# JlinkV9SCH.net
KiCad netlist of a schematic drawn in Altium Designer
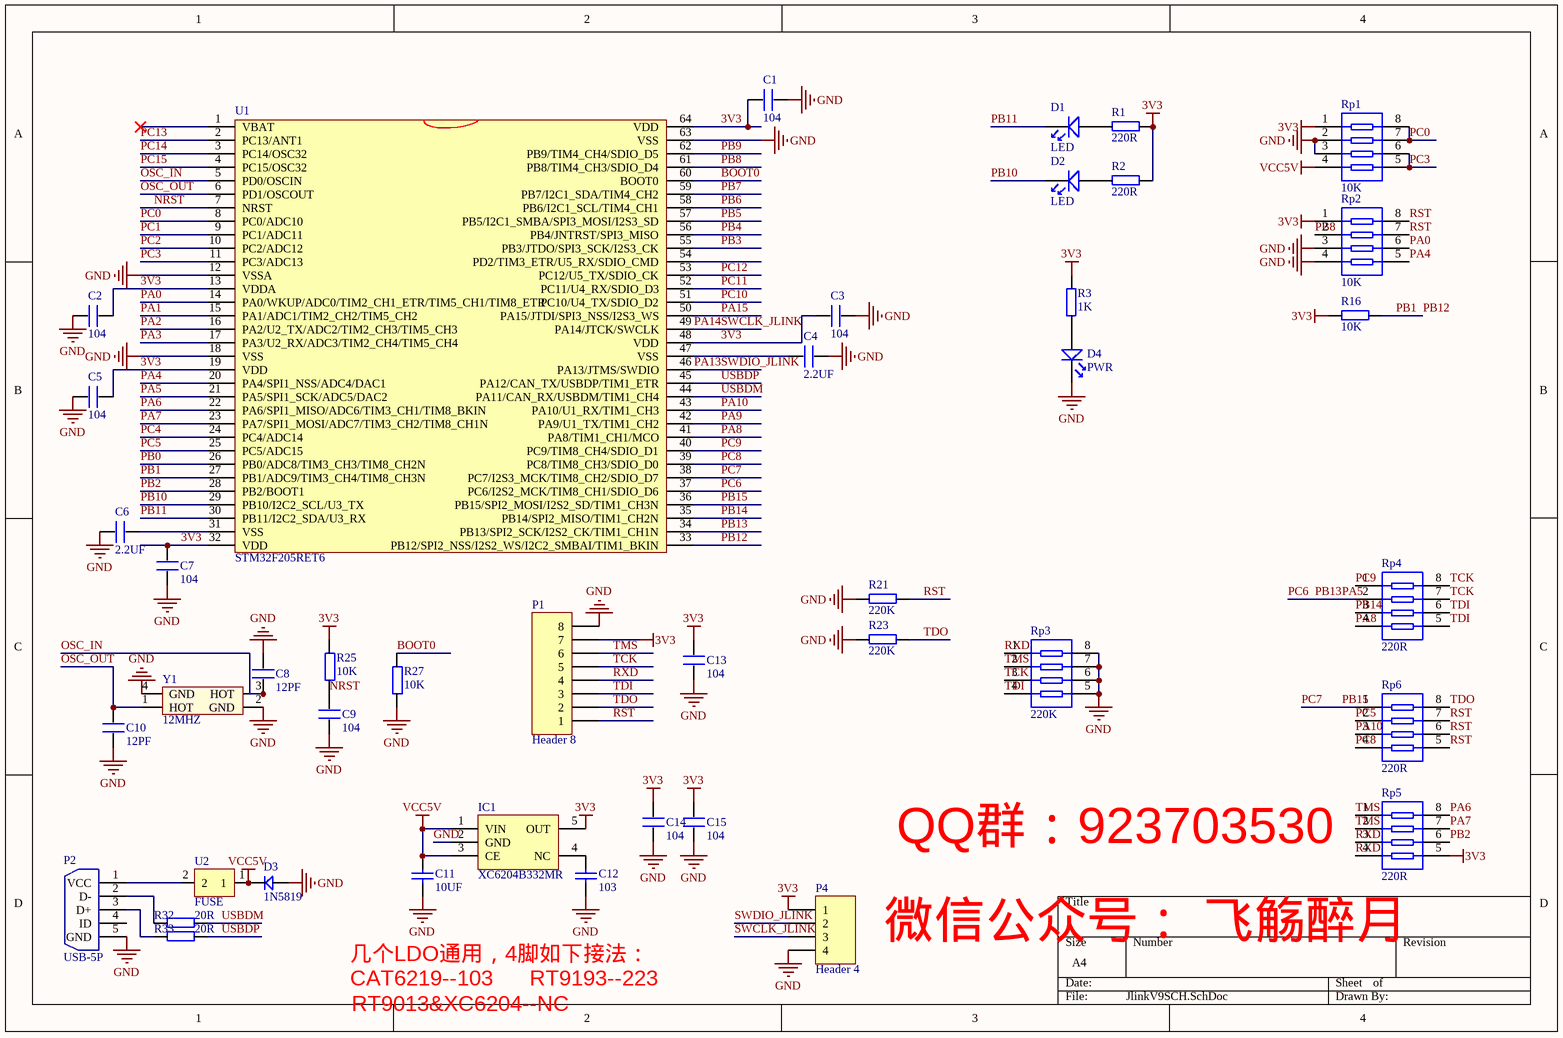
[diagram p0: JlinkV9SCH.SchDoc]

(export (version "E")
  (design (tool "Eeschema 10.0.6"))
  (components
    (comp (ref "C1") (value "104") (footprint "0402_C") (libsource (lib "myschlib") (part "C")))
    (comp (ref "C2") (value "104") (footprint "0402_C") (libsource (lib "myschlib") (part "C")))
    (comp (ref "C3") (value "104") (footprint "0402_C") (libsource (lib "myschlib") (part "C")))
    (comp (ref "C4") (value "2.2UF") (footprint "0402_C") (libsource (lib "myschlib") (part "C")))
    (comp (ref "C5") (value "104") (footprint "0402_C") (libsource (lib "myschlib") (part "C")))
    (comp (ref "C6") (value "2.2UF") (footprint "0402_C") (libsource (lib "myschlib") (part "C")))
    (comp (ref "C7") (value "104") (footprint "0402_C") (libsource (lib "myschlib") (part "C")))
    (comp (ref "C8") (value "12PF") (footprint "0402_C") (libsource (lib "myschlib") (part "C")))
    (comp (ref "C9") (value "104") (footprint "0402_C") (libsource (lib "myschlib") (part "C")))
    (comp (ref "C10") (value "12PF") (footprint "0402_C") (libsource (lib "myschlib") (part "C")))
    (comp (ref "C11")
      (value "10UF")
      (footprint "0603_C")
      (description "贴片电容")
      (libsource (lib "Miscellaneous Devices LC") (part "0603 10uF (106) 10% 10V"))
    )
    (comp (ref "C12")
      (value "103")
      (footprint "0402_C")
      (description "贴片电容")
      (libsource (lib "Miscellaneous Devices LC") (part "0402 10nF (103) 10% 50V"))
    )
    (comp (ref "C13") (value "104") (footprint "0603_C") (libsource (lib "myschlib") (part "C")))
    (comp (ref "C14") (value "104") (footprint "0603_C") (libsource (lib "myschlib") (part "C")))
    (comp (ref "C15") (value "104") (footprint "0603_C") (libsource (lib "myschlib") (part "C")))
    (comp (ref "D1") (value "LED") (footprint "SMDLED-0603") (libsource (lib "myschlib") (part "LED")))
    (comp (ref "D2") (value "LED") (footprint "SMDLED-0603") (libsource (lib "myschlib") (part "LED")))
    (comp (ref "D3") (value "1N5819") (footprint "mypcblib:SOD-323") (libsource (lib "myschlib") (part "D")))
    (comp (ref "D4") (value "PWR") (footprint "SMDLED-0603") (libsource (lib "myschlib") (part "LED")))
    (comp (ref "IC1")
      (value "XC6204B332MR")
      (footprint "SOT23-5L")
      (description "LDO")
      (fields (field (name "版权归属") "源创客"))
      (libsource (lib "myschlib") (part "LDO XC6204"))
    )
    (comp (ref "P1")
      (value "Header 8")
      (footprint "GH1.25-8P")
      (description "Header, 8-Pin")
      (fields (field (name "PUBLISHER") "Altium Limited"))
      (libsource (lib "myschlib") (part "Header 8"))
    )
    (comp (ref "P2")
      (value "USB-5P")
      (footprint "MICRO_USB")
      (description "微型USB母座")
      (fields (field (name "版权归属") "源创客"))
      (libsource (lib "myschlib") (part "USB-5P"))
    )
    (comp (ref "P4")
      (value "Header 4")
      (footprint "HDR1X4_SMD")
      (description "Header, 4-Pin")
      (fields (field (name "PUBLISHER") "Altium Limited"))
      (libsource (lib "myschlib") (part "Header 4"))
    )
    (comp (ref "R1") (value "220R") (footprint "0402_R") (libsource (lib "myschlib") (part "R")))
    (comp (ref "R2") (value "220R") (footprint "0402_R") (libsource (lib "myschlib") (part "R")))
    (comp (ref "R3") (value "1K") (footprint "0402_R") (libsource (lib "myschlib") (part "R")))
    (comp (ref "R16") (value "10K") (footprint "0402_R") (libsource (lib "myschlib") (part "R")))
    (comp (ref "R21") (value "220K") (footprint "0402_R") (libsource (lib "myschlib") (part "R")))
    (comp (ref "R23") (value "220K") (footprint "0402_R") (libsource (lib "myschlib") (part "R")))
    (comp (ref "R25") (value "10K") (footprint "0402_R") (libsource (lib "myschlib") (part "R")))
    (comp (ref "R27") (value "10K") (footprint "0402_R") (libsource (lib "myschlib") (part "R")))
    (comp (ref "R32") (value "20R") (footprint "0402_R") (libsource (lib "myschlib") (part "R")))
    (comp (ref "R33") (value "20R") (footprint "0402_R") (libsource (lib "myschlib") (part "R")))
    (comp (ref "Rp1")
      (value "10K")
      (footprint "mypcblib:0402_Rx4")
      (description "贴片排阻")
      (libsource (lib "myschlib") (part "R*4"))
    )
    (comp (ref "Rp2")
      (value "10K")
      (footprint "mypcblib:0402_Rx4")
      (description "贴片排阻")
      (libsource (lib "myschlib") (part "R*4"))
    )
    (comp (ref "Rp3")
      (value "220K")
      (footprint "mypcblib:0402_Rx4")
      (description "贴片排阻")
      (libsource (lib "myschlib") (part "R*4"))
    )
    (comp (ref "Rp4")
      (value "220R")
      (footprint "mypcblib:0402_Rx4")
      (description "贴片排阻")
      (libsource (lib "myschlib") (part "R*4"))
    )
    (comp (ref "Rp5")
      (value "220R")
      (footprint "mypcblib:0402_Rx4")
      (description "贴片排阻")
      (libsource (lib "myschlib") (part "R*4"))
    )
    (comp (ref "Rp6")
      (value "220R")
      (footprint "mypcblib:0402_Rx4")
      (description "贴片排阻")
      (libsource (lib "myschlib") (part "R*4"))
    )
    (comp (ref "U1")
      (value "STM32F205RET6")
      (footprint "STM-LQFP64_M")
      (libsource (lib "myschlib") (part "STM32F103RET6"))
    )
    (comp (ref "U2") (value "FUSE") (footprint "0603P") (libsource (lib "myschlib") (part "FUSE")))
    (comp (ref "Y1")
      (value "12MHZ")
      (footprint "XTAL3225")
      (description "3225贴片无源晶振")
      (libsource (lib "myschlib") (part "XTAL_3225"))
    )
  )
  (nets
    (net (code "1") (name "/BOOT0") (class "Default")
      (node (ref "R27") (pin "2") (pintype "passive"))
      (node (ref "U1") (pin "60") (pinfunction "BOOT0_60") (pintype "passive"))
    )
    (net (code "2") (name "/NRST") (class "Default")
      (node (ref "C9") (pin "2") (pintype "passive"))
      (node (ref "R25") (pin "1") (pintype "passive"))
      (node (ref "U1") (pin "7") (pinfunction "NRST_7") (pintype "passive"))
    )
    (net (code "3") (name "/OSC_IN") (class "Default")
      (node (ref "C8") (pin "1") (pintype "passive"))
      (node (ref "U1") (pin "5") (pinfunction "PD0/OSCIN_5") (pintype "passive"))
      (node (ref "Y1") (pin "3") (pinfunction "HOT_3") (pintype "passive"))
    )
    (net (code "4") (name "/OSC_OUT") (class "Default")
      (node (ref "C10") (pin "2") (pintype "passive"))
      (node (ref "U1") (pin "6") (pinfunction "PD1/OSCOUT_6") (pintype "passive"))
      (node (ref "Y1") (pin "1") (pinfunction "HOT_1") (pintype "passive"))
    )
    (net (code "5") (name "/PA0") (class "Default")
      (node (ref "Rp2") (pin "6") (pinfunction "6_6") (pintype "passive"))
      (node (ref "U1") (pin "14") (pinfunction "PA0/WKUP/ADC0/TIM2_CH1_ETR/TIM5_CH1/TIM8_ETR_14") (pintype "passive"))
    )
    (net (code "6") (name "/PA1") (class "Default")
      (node (ref "U1") (pin "15") (pinfunction "PA1/ADC1/TIM2_CH2/TIM5_CH2_15") (pintype "passive"))
    )
    (net (code "7") (name "/PA2") (class "Default")
      (node (ref "U1") (pin "16") (pinfunction "PA2/U2_TX/ADC2/TIM2_CH3/TIM5_CH3_16") (pintype "passive"))
    )
    (net (code "8") (name "/PA3") (class "Default")
      (node (ref "U1") (pin "17") (pinfunction "PA3/U2_RX/ADC3/TIM2_CH4/TIM5_CH4_17") (pintype "passive"))
    )
    (net (code "9") (name "/PA4") (class "Default")
      (node (ref "Rp2") (pin "5") (pinfunction "5_5") (pintype "passive"))
      (node (ref "U1") (pin "20") (pinfunction "PA4/SPI1_NSS/ADC4/DAC1_20") (pintype "passive"))
    )
    (net (code "10") (name "/PA5") (class "Default")
      (node (ref "Rp4") (pin "2") (pinfunction "2_2") (pintype "passive"))
      (node (ref "U1") (pin "21") (pinfunction "PA5/SPI1_SCK/ADC5/DAC2_21") (pintype "passive"))
      (node (ref "U1") (pin "34") (pinfunction "PB13/SPI2_SCK/I2S2_CK/TIM1_CH1N_34") (pintype "passive"))
      (node (ref "U1") (pin "37") (pinfunction "PC6/I2S2_MCK/TIM8_CH1/SDIO_D6_37") (pintype "passive"))
    )
    (net (code "11") (name "/PA6") (class "Default")
      (node (ref "Rp5") (pin "8") (pinfunction "8_8") (pintype "passive"))
      (node (ref "U1") (pin "22") (pinfunction "PA6/SPI1_MISO/ADC6/TIM3_CH1/TIM8_BKIN_22") (pintype "passive"))
    )
    (net (code "12") (name "/PA7") (class "Default")
      (node (ref "Rp5") (pin "7") (pinfunction "7_7") (pintype "passive"))
      (node (ref "U1") (pin "23") (pinfunction "PA7/SPI1_MOSI/ADC7/TIM3_CH2/TIM8_CH1N_23") (pintype "passive"))
    )
    (net (code "13") (name "/PA8") (class "Default")
      (node (ref "Rp4") (pin "4") (pinfunction "4_4") (pintype "passive"))
      (node (ref "U1") (pin "41") (pinfunction "PA8/TIM1_CH1/MCO_41") (pintype "passive"))
    )
    (net (code "14") (name "/PA9") (class "Default")
      (node (ref "U1") (pin "42") (pinfunction "PA9/U1_TX/TIM1_CH2_42") (pintype "passive"))
    )
    (net (code "15") (name "/PA10") (class "Default")
      (node (ref "Rp6") (pin "3") (pinfunction "3_3") (pintype "passive"))
      (node (ref "U1") (pin "43") (pinfunction "PA10/U1_RX/TIM1_CH3_43") (pintype "passive"))
    )
    (net (code "16") (name "/PA13") (class "Default")
      (node (ref "P4") (pin "2") (pinfunction "2_2") (pintype "passive"))
      (node (ref "U1") (pin "46") (pinfunction "PA13/JTMS/SWDIO_46") (pintype "passive"))
    )
    (net (code "17") (name "/PA14") (class "Default")
      (node (ref "P4") (pin "3") (pinfunction "3_3") (pintype "passive"))
      (node (ref "U1") (pin "49") (pinfunction "PA14/JTCK/SWCLK_49") (pintype "passive"))
    )
    (net (code "18") (name "/PA15") (class "Default")
      (node (ref "U1") (pin "50") (pinfunction "PA15/JTDI/SPI3_NSS/I2S3_WS_50") (pintype "passive"))
    )
    (net (code "19") (name "/PB0") (class "Default")
      (node (ref "U1") (pin "26") (pinfunction "PB0/ADC8/TIM3_CH3/TIM8_CH2N_26") (pintype "passive"))
    )
    (net (code "20") (name "/PB1") (class "Default")
      (node (ref "R16") (pin "1") (pintype "passive"))
      (node (ref "U1") (pin "27") (pinfunction "PB1/ADC9/TIM3_CH4/TIM8_CH3N_27") (pintype "passive"))
      (node (ref "U1") (pin "33") (pinfunction "PB12/SPI2_NSS/I2S2_WS/I2C2_SMBAI/TIM1_BKIN_33") (pintype "passive"))
    )
    (net (code "21") (name "/PB2") (class "Default")
      (node (ref "Rp5") (pin "6") (pinfunction "6_6") (pintype "passive"))
      (node (ref "U1") (pin "28") (pinfunction "PB2/BOOT1_28") (pintype "passive"))
    )
    (net (code "22") (name "/PB3") (class "Default")
      (node (ref "U1") (pin "55") (pinfunction "PB3/JTDO/SPI3_SCK/I2S3_CK_55") (pintype "passive"))
    )
    (net (code "23") (name "/PB4") (class "Default")
      (node (ref "U1") (pin "56") (pinfunction "PB4/JNTRST/SPI3_MISO_56") (pintype "passive"))
    )
    (net (code "24") (name "/PB5") (class "Default")
      (node (ref "U1") (pin "57") (pinfunction "PB5/I2C1_SMBA/SPI3_MOSI/I2S3_SD_57") (pintype "passive"))
    )
    (net (code "25") (name "/PB6") (class "Default")
      (node (ref "U1") (pin "58") (pinfunction "PB6/I2C1_SCL/TIM4_CH1_58") (pintype "passive"))
    )
    (net (code "26") (name "/PB7") (class "Default")
      (node (ref "U1") (pin "59") (pinfunction "PB7/I2C1_SDA/TIM4_CH2_59") (pintype "passive"))
    )
    (net (code "27") (name "/PB8") (class "Default")
      (node (ref "Rp2") (pin "2") (pinfunction "2_2") (pintype "passive"))
      (node (ref "U1") (pin "61") (pinfunction "PB8/TIM4_CH3/SDIO_D4_61") (pintype "passive"))
    )
    (net (code "28") (name "/PB9") (class "Default")
      (node (ref "U1") (pin "62") (pinfunction "PB9/TIM4_CH4/SDIO_D5_62") (pintype "passive"))
    )
    (net (code "29") (name "/PB10") (class "Default")
      (node (ref "D2") (pin "2") (pinfunction "2_2") (pintype "passive"))
      (node (ref "U1") (pin "29") (pinfunction "PB10/I2C2_SCL/U3_TX_29") (pintype "passive"))
    )
    (net (code "30") (name "/PB11") (class "Default")
      (node (ref "D1") (pin "2") (pinfunction "2_2") (pintype "passive"))
      (node (ref "U1") (pin "30") (pinfunction "PB11/I2C2_SDA/U3_RX_30") (pintype "passive"))
    )
    (net (code "31") (name "/PB14") (class "Default")
      (node (ref "Rp4") (pin "3") (pinfunction "3_3") (pintype "passive"))
      (node (ref "U1") (pin "35") (pinfunction "PB14/SPI2_MISO/TIM1_CH2N_35") (pintype "passive"))
    )
    (net (code "32") (name "/PB15") (class "Default")
      (node (ref "Rp6") (pin "1") (pinfunction "1_1") (pintype "passive"))
      (node (ref "U1") (pin "36") (pinfunction "PB15/SPI2_MOSI/I2S2_SD/TIM1_CH3N_36") (pintype "passive"))
      (node (ref "U1") (pin "38") (pinfunction "PC7/I2S3_MCK/TIM8_CH2/SDIO_D7_38") (pintype "passive"))
    )
    (net (code "33") (name "/PC0") (class "Default")
      (node (ref "Rp1") (pin "7") (pinfunction "7_7") (pintype "passive"))
      (node (ref "Rp1") (pin "8") (pinfunction "8_8") (pintype "passive"))
      (node (ref "U1") (pin "8") (pinfunction "PC0/ADC10_8") (pintype "passive"))
    )
    (net (code "34") (name "/PC1") (class "Default")
      (node (ref "U1") (pin "9") (pinfunction "PC1/ADC11_9") (pintype "passive"))
    )
    (net (code "35") (name "/PC2") (class "Default")
      (node (ref "U1") (pin "10") (pinfunction "PC2/ADC12_10") (pintype "passive"))
    )
    (net (code "36") (name "/PC3") (class "Default")
      (node (ref "Rp1") (pin "5") (pinfunction "5_5") (pintype "passive"))
      (node (ref "Rp1") (pin "6") (pinfunction "6_6") (pintype "passive"))
      (node (ref "U1") (pin "11") (pinfunction "PC3/ADC13_11") (pintype "passive"))
    )
    (net (code "37") (name "/PC4") (class "Default")
      (node (ref "U1") (pin "24") (pinfunction "PC4/ADC14_24") (pintype "passive"))
    )
    (net (code "38") (name "/PC5") (class "Default")
      (node (ref "Rp6") (pin "2") (pinfunction "2_2") (pintype "passive"))
      (node (ref "U1") (pin "25") (pinfunction "PC5/ADC15_25") (pintype "passive"))
    )
    (net (code "39") (name "/PC8") (class "Default")
      (node (ref "Rp6") (pin "4") (pinfunction "4_4") (pintype "passive"))
      (node (ref "U1") (pin "39") (pinfunction "PC8/TIM8_CH3/SDIO_D0_39") (pintype "passive"))
    )
    (net (code "40") (name "/PC9") (class "Default")
      (node (ref "Rp4") (pin "1") (pinfunction "1_1") (pintype "passive"))
      (node (ref "U1") (pin "40") (pinfunction "PC9/TIM8_CH4/SDIO_D1_40") (pintype "passive"))
    )
    (net (code "41") (name "/PC10") (class "Default")
      (node (ref "U1") (pin "51") (pinfunction "PC10/U4_TX/SDIO_D2_51") (pintype "passive"))
    )
    (net (code "42") (name "/PC11") (class "Default")
      (node (ref "U1") (pin "52") (pinfunction "PC11/U4_RX/SDIO_D3_52") (pintype "passive"))
    )
    (net (code "43") (name "/PC12") (class "Default")
      (node (ref "U1") (pin "53") (pinfunction "PC12/U5_TX/SDIO_CK_53") (pintype "passive"))
    )
    (net (code "44") (name "/PC13") (class "Default")
      (node (ref "U1") (pin "2") (pinfunction "PC13/ANT1_2") (pintype "passive"))
    )
    (net (code "45") (name "/PC14") (class "Default")
      (node (ref "U1") (pin "3") (pinfunction "PC14/OSC32_3") (pintype "passive"))
    )
    (net (code "46") (name "/PC15") (class "Default")
      (node (ref "U1") (pin "4") (pinfunction "PC15/OSC32_4") (pintype "passive"))
    )
    (net (code "47") (name "/RST") (class "Default")
      (node (ref "P1") (pin "1") (pinfunction "1_1") (pintype "passive"))
      (node (ref "R21") (pin "1") (pintype "passive"))
      (node (ref "Rp2") (pin "7") (pinfunction "7_7") (pintype "passive"))
      (node (ref "Rp2") (pin "8") (pinfunction "8_8") (pintype "passive"))
      (node (ref "Rp6") (pin "5") (pinfunction "5_5") (pintype "passive"))
      (node (ref "Rp6") (pin "6") (pinfunction "6_6") (pintype "passive"))
      (node (ref "Rp6") (pin "7") (pinfunction "7_7") (pintype "passive"))
    )
    (net (code "48") (name "/RXD") (class "Default")
      (node (ref "P1") (pin "4") (pinfunction "4_4") (pintype "passive"))
      (node (ref "Rp3") (pin "1") (pinfunction "1_1") (pintype "passive"))
      (node (ref "Rp5") (pin "3") (pinfunction "3_3") (pintype "passive"))
      (node (ref "Rp5") (pin "4") (pinfunction "4_4") (pintype "passive"))
    )
    (net (code "49") (name "/TCK") (class "Default")
      (node (ref "P1") (pin "5") (pinfunction "5_5") (pintype "passive"))
      (node (ref "Rp3") (pin "3") (pinfunction "3_3") (pintype "passive"))
      (node (ref "Rp4") (pin "7") (pinfunction "7_7") (pintype "passive"))
      (node (ref "Rp4") (pin "8") (pinfunction "8_8") (pintype "passive"))
    )
    (net (code "50") (name "/TDI") (class "Default")
      (node (ref "P1") (pin "3") (pinfunction "3_3") (pintype "passive"))
      (node (ref "Rp3") (pin "4") (pinfunction "4_4") (pintype "passive"))
      (node (ref "Rp4") (pin "5") (pinfunction "5_5") (pintype "passive"))
      (node (ref "Rp4") (pin "6") (pinfunction "6_6") (pintype "passive"))
    )
    (net (code "51") (name "/TDO") (class "Default")
      (node (ref "P1") (pin "2") (pinfunction "2_2") (pintype "passive"))
      (node (ref "R23") (pin "1") (pintype "passive"))
      (node (ref "Rp6") (pin "8") (pinfunction "8_8") (pintype "passive"))
    )
    (net (code "52") (name "/TMS") (class "Default")
      (node (ref "P1") (pin "6") (pinfunction "6_6") (pintype "passive"))
      (node (ref "Rp3") (pin "2") (pinfunction "2_2") (pintype "passive"))
      (node (ref "Rp5") (pin "1") (pinfunction "1_1") (pintype "passive"))
      (node (ref "Rp5") (pin "2") (pinfunction "2_2") (pintype "passive"))
    )
    (net (code "53") (name "/USBDM") (class "Default")
      (node (ref "R32") (pin "1") (pintype "passive"))
      (node (ref "U1") (pin "44") (pinfunction "PA11/CAN_RX/USBDM/TIM1_CH4_44") (pintype "passive"))
    )
    (net (code "54") (name "/USBDP") (class "Default")
      (node (ref "R33") (pin "1") (pintype "passive"))
      (node (ref "U1") (pin "45") (pinfunction "PA12/CAN_TX/USBDP/TIM1_ETR_45") (pintype "passive"))
    )
    (net (code "55") (name "3V3") (class "Default")
      (node (ref "C1") (pin "2") (pintype "passive"))
      (node (ref "C13") (pin "2") (pintype "passive"))
      (node (ref "C14") (pin "2") (pintype "passive"))
      (node (ref "C15") (pin "2") (pintype "passive"))
      (node (ref "C2") (pin "1") (pintype "passive"))
      (node (ref "C3") (pin "2") (pintype "passive"))
      (node (ref "C5") (pin "1") (pintype "passive"))
      (node (ref "C7") (pin "2") (pintype "passive"))
      (node (ref "IC1") (pin "5") (pinfunction "OUT_5") (pintype "passive"))
      (node (ref "P1") (pin "7") (pinfunction "7_7") (pintype "passive"))
      (node (ref "P4") (pin "1") (pinfunction "1_1") (pintype "passive"))
      (node (ref "R1") (pin "1") (pintype "passive"))
      (node (ref "R16") (pin "2") (pintype "passive"))
      (node (ref "R2") (pin "1") (pintype "passive"))
      (node (ref "R25") (pin "2") (pintype "passive"))
      (node (ref "R3") (pin "1") (pintype "passive"))
      (node (ref "Rp1") (pin "1") (pinfunction "1_1") (pintype "passive"))
      (node (ref "Rp2") (pin "1") (pinfunction "1_1") (pintype "passive"))
      (node (ref "Rp5") (pin "5") (pinfunction "5_5") (pintype "passive"))
      (node (ref "U1") (pin "13") (pinfunction "VDDA_13") (pintype "passive"))
      (node (ref "U1") (pin "19") (pinfunction "VDD_19") (pintype "passive"))
      (node (ref "U1") (pin "32") (pinfunction "VDD_32") (pintype "passive"))
      (node (ref "U1") (pin "48") (pinfunction "VDD_48") (pintype "passive"))
      (node (ref "U1") (pin "64") (pinfunction "VDD_64") (pintype "passive"))
    )
    (net (code "56") (name "GND") (class "Default")
      (node (ref "C1") (pin "1") (pintype "passive"))
      (node (ref "C10") (pin "1") (pintype "passive"))
      (node (ref "C11") (pin "1") (pinfunction "1_1") (pintype "passive"))
      (node (ref "C12") (pin "1") (pinfunction "1_1") (pintype "passive"))
      (node (ref "C13") (pin "1") (pintype "passive"))
      (node (ref "C14") (pin "1") (pintype "passive"))
      (node (ref "C15") (pin "1") (pintype "passive"))
      (node (ref "C2") (pin "2") (pintype "passive"))
      (node (ref "C3") (pin "1") (pintype "passive"))
      (node (ref "C4") (pin "2") (pintype "passive"))
      (node (ref "C5") (pin "2") (pintype "passive"))
      (node (ref "C6") (pin "2") (pintype "passive"))
      (node (ref "C7") (pin "1") (pintype "passive"))
      (node (ref "C8") (pin "2") (pintype "passive"))
      (node (ref "C9") (pin "1") (pintype "passive"))
      (node (ref "D3") (pin "1") (pintype "passive"))
      (node (ref "D4") (pin "2") (pinfunction "2_2") (pintype "passive"))
      (node (ref "IC1") (pin "2") (pinfunction "GND_2") (pintype "passive"))
      (node (ref "P1") (pin "8") (pinfunction "8_8") (pintype "passive"))
      (node (ref "P2") (pin "5") (pinfunction "GND_5") (pintype "passive"))
      (node (ref "P4") (pin "4") (pinfunction "4_4") (pintype "passive"))
      (node (ref "R21") (pin "2") (pintype "passive"))
      (node (ref "R23") (pin "2") (pintype "passive"))
      (node (ref "R27") (pin "1") (pintype "passive"))
      (node (ref "Rp1") (pin "2") (pinfunction "2_2") (pintype "passive"))
      (node (ref "Rp1") (pin "3") (pinfunction "3_3") (pintype "passive"))
      (node (ref "Rp2") (pin "3") (pinfunction "3_3") (pintype "passive"))
      (node (ref "Rp2") (pin "4") (pinfunction "4_4") (pintype "passive"))
      (node (ref "Rp3") (pin "5") (pinfunction "5_5") (pintype "passive"))
      (node (ref "Rp3") (pin "6") (pinfunction "6_6") (pintype "passive"))
      (node (ref "Rp3") (pin "7") (pinfunction "7_7") (pintype "passive"))
      (node (ref "Rp3") (pin "8") (pinfunction "8_8") (pintype "passive"))
      (node (ref "U1") (pin "12") (pinfunction "VSSA_12") (pintype "passive"))
      (node (ref "U1") (pin "18") (pinfunction "VSS_18") (pintype "passive"))
      (node (ref "U1") (pin "63") (pinfunction "VSS_63") (pintype "passive"))
      (node (ref "Y1") (pin "2") (pinfunction "GND_2") (pintype "passive"))
      (node (ref "Y1") (pin "4") (pinfunction "GND_4") (pintype "passive"))
    )
    (net (code "57") (name "Net-(C4-Pad1)") (class "Default")
      (node (ref "C4") (pin "1") (pintype "passive"))
      (node (ref "U1") (pin "47") (pinfunction "VSS_47") (pintype "passive"))
    )
    (net (code "58") (name "Net-(C6-Pad1)") (class "Default")
      (node (ref "C6") (pin "1") (pintype "passive"))
      (node (ref "U1") (pin "31") (pinfunction "VSS_31") (pintype "passive"))
    )
    (net (code "59") (name "Net-(D1-Pad1)") (class "Default")
      (node (ref "D1") (pin "1") (pinfunction "1_1") (pintype "passive"))
      (node (ref "R1") (pin "2") (pintype "passive"))
    )
    (net (code "60") (name "Net-(D2-Pad1)") (class "Default")
      (node (ref "D2") (pin "1") (pinfunction "1_1") (pintype "passive"))
      (node (ref "R2") (pin "2") (pintype "passive"))
    )
    (net (code "61") (name "Net-(D4-Pad1)") (class "Default")
      (node (ref "D4") (pin "1") (pinfunction "1_1") (pintype "passive"))
      (node (ref "R3") (pin "2") (pintype "passive"))
    )
    (net (code "62") (name "Net-(IC1-NC)") (class "Default")
      (node (ref "C12") (pin "2") (pinfunction "2_2") (pintype "passive"))
      (node (ref "IC1") (pin "4") (pinfunction "NC_4") (pintype "passive"))
    )
    (net (code "63") (name "Net-(P2-D+)") (class "Default")
      (node (ref "P2") (pin "3") (pinfunction "D+_3") (pintype "passive"))
      (node (ref "R33") (pin "2") (pintype "passive"))
    )
    (net (code "64") (name "Net-(P2-D-)") (class "Default")
      (node (ref "P2") (pin "2") (pinfunction "D-_2") (pintype "passive"))
      (node (ref "R32") (pin "2") (pintype "passive"))
    )
    (net (code "65") (name "Net-(P2-VCC)") (class "Default")
      (node (ref "P2") (pin "1") (pinfunction "VCC_1") (pintype "passive"))
      (node (ref "U2") (pin "2") (pinfunction "2_2") (pintype "passive"))
    )
    (net (code "66") (name "VCC5V") (class "Default")
      (node (ref "C11") (pin "2") (pinfunction "2_2") (pintype "passive"))
      (node (ref "D3") (pin "2") (pintype "passive"))
      (node (ref "IC1") (pin "1") (pinfunction "VIN_1") (pintype "passive"))
      (node (ref "IC1") (pin "3") (pinfunction "CE_3") (pintype "passive"))
      (node (ref "Rp1") (pin "4") (pinfunction "4_4") (pintype "passive"))
      (node (ref "U2") (pin "1") (pinfunction "1_1") (pintype "passive"))
    )
    (net (code "67") (name "unconnected-(P2-ID-Pad4)") (class "Default")
      (node (ref "P2") (pin "4") (pinfunction "ID_4") (pintype "passive"))
    )
    (net (code "68") (name "unconnected-(U1-PD2{slash}TIM3_ETR{slash}U5_RX{slash}SDIO_CMD-Pad54)") (class "Default")
      (node (ref "U1") (pin "54") (pinfunction "PD2/TIM3_ETR/U5_RX/SDIO_CMD_54") (pintype "passive"))
    )
    (net (code "69") (name "unconnected-(U1-VBAT-Pad1)") (class "Default")
      (node (ref "U1") (pin "1") (pinfunction "VBAT_1") (pintype "passive+no_connect"))
    )
  )
)
